# visualization_breakout_4_port.net
KiCad netlist of a schematic drawn in EAGLE
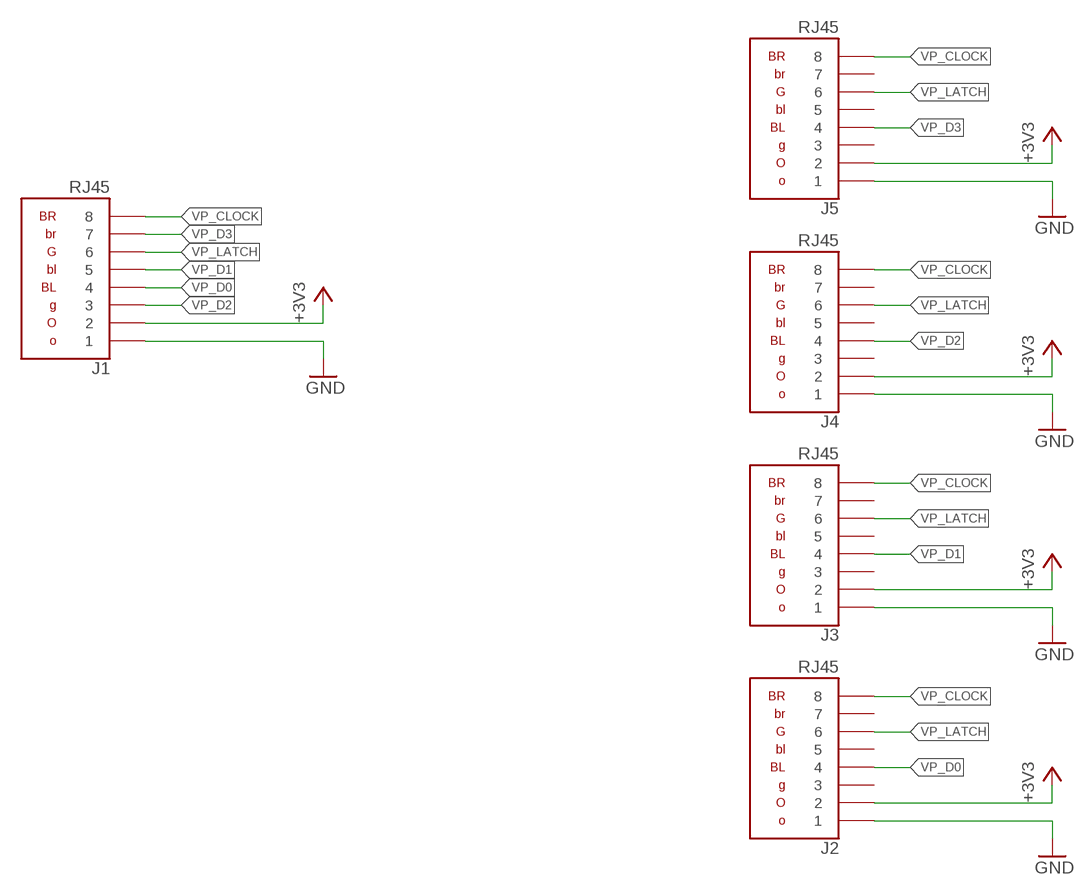
[diagram p0: schematic, sheet 1]

(export (version "E")
  (design (tool "Eeschema 10.0.6"))
  (components
    (comp (ref "J1")
      (value "RJ45")
      (footprint "eagle-import:RJ45")
      (libsource (lib "eagle-import") (part "RJ45"))
    )
    (comp (ref "J2")
      (value "RJ45")
      (footprint "eagle-import:RJ45")
      (libsource (lib "eagle-import") (part "RJ45"))
    )
    (comp (ref "J3")
      (value "RJ45")
      (footprint "eagle-import:RJ45")
      (libsource (lib "eagle-import") (part "RJ45"))
    )
    (comp (ref "J4")
      (value "RJ45")
      (footprint "eagle-import:RJ45")
      (libsource (lib "eagle-import") (part "RJ45"))
    )
    (comp (ref "J5")
      (value "RJ45")
      (footprint "eagle-import:RJ45")
      (libsource (lib "eagle-import") (part "RJ45"))
    )
  )
  (nets
    (net (code "1") (name "+3V3") (class "Default")
      (node (ref "J1") (pin "2") (pinfunction "2_2") (pintype "bidirectional"))
      (node (ref "J2") (pin "2") (pinfunction "2_2") (pintype "bidirectional"))
      (node (ref "J3") (pin "2") (pinfunction "2_2") (pintype "bidirectional"))
      (node (ref "J4") (pin "2") (pinfunction "2_2") (pintype "bidirectional"))
      (node (ref "J5") (pin "2") (pinfunction "2_2") (pintype "bidirectional"))
    )
    (net (code "2") (name "GND") (class "Default")
      (node (ref "J1") (pin "1") (pinfunction "1_1") (pintype "bidirectional"))
      (node (ref "J2") (pin "1") (pinfunction "1_1") (pintype "bidirectional"))
      (node (ref "J3") (pin "1") (pinfunction "1_1") (pintype "bidirectional"))
      (node (ref "J4") (pin "1") (pinfunction "1_1") (pintype "bidirectional"))
      (node (ref "J5") (pin "1") (pinfunction "1_1") (pintype "bidirectional"))
    )
    (net (code "3") (name "VP_CLOCK") (class "Default")
      (node (ref "J1") (pin "8") (pinfunction "8_8") (pintype "bidirectional"))
      (node (ref "J2") (pin "8") (pinfunction "8_8") (pintype "bidirectional"))
      (node (ref "J3") (pin "8") (pinfunction "8_8") (pintype "bidirectional"))
      (node (ref "J4") (pin "8") (pinfunction "8_8") (pintype "bidirectional"))
      (node (ref "J5") (pin "8") (pinfunction "8_8") (pintype "bidirectional"))
    )
    (net (code "4") (name "VP_D0") (class "Default")
      (node (ref "J1") (pin "4") (pinfunction "4_4") (pintype "bidirectional"))
      (node (ref "J2") (pin "4") (pinfunction "4_4") (pintype "bidirectional"))
    )
    (net (code "5") (name "VP_D1") (class "Default")
      (node (ref "J1") (pin "5") (pinfunction "5_5") (pintype "bidirectional"))
      (node (ref "J3") (pin "4") (pinfunction "4_4") (pintype "bidirectional"))
    )
    (net (code "6") (name "VP_D2") (class "Default")
      (node (ref "J1") (pin "3") (pinfunction "3_3") (pintype "bidirectional"))
      (node (ref "J4") (pin "4") (pinfunction "4_4") (pintype "bidirectional"))
    )
    (net (code "7") (name "VP_D3") (class "Default")
      (node (ref "J1") (pin "7") (pinfunction "7_7") (pintype "bidirectional"))
      (node (ref "J5") (pin "4") (pinfunction "4_4") (pintype "bidirectional"))
    )
    (net (code "8") (name "VP_LATCH") (class "Default")
      (node (ref "J1") (pin "6") (pinfunction "6_6") (pintype "bidirectional"))
      (node (ref "J2") (pin "6") (pinfunction "6_6") (pintype "bidirectional"))
      (node (ref "J3") (pin "6") (pinfunction "6_6") (pintype "bidirectional"))
      (node (ref "J4") (pin "6") (pinfunction "6_6") (pintype "bidirectional"))
      (node (ref "J5") (pin "6") (pinfunction "6_6") (pintype "bidirectional"))
    )
    (net (code "9") (name "unconnected-(J2-Pad3)") (class "Default")
      (node (ref "J2") (pin "3") (pinfunction "3_3") (pintype "bidirectional"))
    )
    (net (code "10") (name "unconnected-(J2-Pad5)") (class "Default")
      (node (ref "J2") (pin "5") (pinfunction "5_5") (pintype "bidirectional"))
    )
    (net (code "11") (name "unconnected-(J2-Pad7)") (class "Default")
      (node (ref "J2") (pin "7") (pinfunction "7_7") (pintype "bidirectional"))
    )
    (net (code "12") (name "unconnected-(J3-Pad3)") (class "Default")
      (node (ref "J3") (pin "3") (pinfunction "3_3") (pintype "bidirectional"))
    )
    (net (code "13") (name "unconnected-(J3-Pad5)") (class "Default")
      (node (ref "J3") (pin "5") (pinfunction "5_5") (pintype "bidirectional"))
    )
    (net (code "14") (name "unconnected-(J3-Pad7)") (class "Default")
      (node (ref "J3") (pin "7") (pinfunction "7_7") (pintype "bidirectional"))
    )
    (net (code "15") (name "unconnected-(J4-Pad3)") (class "Default")
      (node (ref "J4") (pin "3") (pinfunction "3_3") (pintype "bidirectional"))
    )
    (net (code "16") (name "unconnected-(J4-Pad5)") (class "Default")
      (node (ref "J4") (pin "5") (pinfunction "5_5") (pintype "bidirectional"))
    )
    (net (code "17") (name "unconnected-(J4-Pad7)") (class "Default")
      (node (ref "J4") (pin "7") (pinfunction "7_7") (pintype "bidirectional"))
    )
    (net (code "18") (name "unconnected-(J5-Pad3)") (class "Default")
      (node (ref "J5") (pin "3") (pinfunction "3_3") (pintype "bidirectional"))
    )
    (net (code "19") (name "unconnected-(J5-Pad5)") (class "Default")
      (node (ref "J5") (pin "5") (pinfunction "5_5") (pintype "bidirectional"))
    )
    (net (code "20") (name "unconnected-(J5-Pad7)") (class "Default")
      (node (ref "J5") (pin "7") (pinfunction "7_7") (pintype "bidirectional"))
    )
  )
)
